# Sensor.net
KiCad netlist of a schematic drawn in Altium Designer
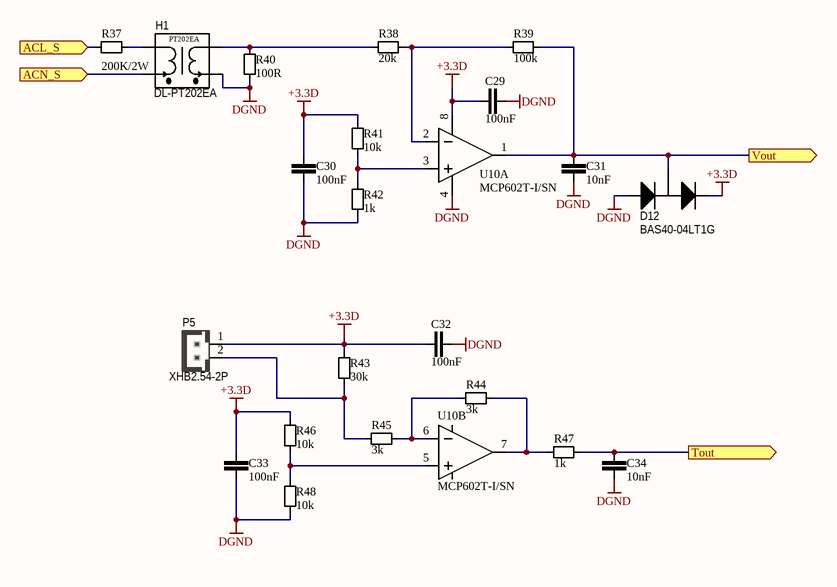
[diagram p0: Sensor.SchDoc]

(export (version "E")
  (design (tool "Eeschema 10.0.6"))
  (components
    (comp (ref "C29")
      (value "100nF")
      (footprint "GreenBox:0603-C")
      (description "MLCC 100nF 10% 50V X7R 0603")
      (fields (field (name "Comment") "Cap") (field (name "PUBLISHER") "GreenBox"))
      (libsource (lib "Capacitor") (part "C21C100NK1H0"))
    )
    (comp (ref "C30")
      (value "100nF")
      (footprint "GreenBox:0603-C")
      (description "MLCC 100nF 10% 50V X7R 0603")
      (fields (field (name "Comment") "Cap") (field (name "PUBLISHER") "GreenBox"))
      (libsource (lib "Capacitor") (part "C21C100NK1H0"))
    )
    (comp (ref "C31")
      (value "10nF")
      (footprint "GreenBox:0603-C")
      (description "MLCC 10nF 10% 50V X7R 0603")
      (fields (field (name "Comment") "Cap") (field (name "PUBLISHER") "GreenBox"))
      (libsource (lib "Capacitor") (part "C21C010NK1H0"))
    )
    (comp (ref "C32")
      (value "100nF")
      (footprint "GreenBox:0603-C")
      (description "MLCC 100nF 10% 50V X7R 0603")
      (fields (field (name "Comment") "Cap") (field (name "PUBLISHER") "GreenBox"))
      (libsource (lib "Capacitor") (part "C21C100NK1H0"))
    )
    (comp (ref "C33")
      (value "100nF")
      (footprint "GreenBox:0603-C")
      (description "MLCC 100nF 10% 50V X7R 0603")
      (fields (field (name "Comment") "Cap") (field (name "PUBLISHER") "GreenBox"))
      (libsource (lib "Capacitor") (part "C21C100NK1H0"))
    )
    (comp (ref "C34")
      (value "10nF")
      (footprint "GreenBox:0603-C")
      (description "MLCC 10nF 10% 50V X7R 0603")
      (fields (field (name "Comment") "Cap") (field (name "PUBLISHER") "GreenBox"))
      (libsource (lib "Capacitor") (part "C21C010NK1H0"))
    )
    (comp (ref "D12")
      (value "BAS40-04LT1G")
      (footprint "GreenBox:SOT-23_N")
      (description "Dual Series Schottky Barrier Diode BAS40-04LT1G Vrrm 40V If 0.12A Ir 1uA")
      (fields (field (name "MANUFACTURER") "ON SEMICONDUCTOR") (field (name "PUBLISHER") "GreenBox"))
      (libsource (lib "Diode_Transistor") (part "D742BAS4004O"))
    )
    (comp (ref "H1")
      (value "DL-PT202EA")
      (footprint "GreenBox:DL-PT202EA")
      (description "Voltage Transformer DL-PT202EA 2mA/2mA 0.1")
      (fields (field (name "MANUFACTURER") "南京向上电子科技有限公司") (field (name "PUBLISHER") "GreenBox"))
      (libsource (lib "Sensor") (part "H1DZPT202EAX"))
    )
    (comp (ref "P5")
      (value "XHB2.54-2P")
      (footprint "GreenBox:XH-2")
      (description "Header XHB2.54-2P 2.54mm")
      (fields (field (name "PUBLISHER") "GreenBox"))
      (libsource (lib "Connectors") (part "P6DX02Z25400"))
    )
    (comp (ref "R37")
      (value "200K/2W")
      (footprint "GreenBox:AXIAL-5mm")
      (description "Metal Film Resistor 200KR 1% 2W0 AXIAL 100PPM")
      (fields (field (name "Comment") "Res") (field (name "PUBLISHER") "GreenBox"))
      (libsource (lib "Resistor") (part "RMDA200KFGF0"))
    )
    (comp (ref "R38")
      (value "20k")
      (footprint "GreenBox:0603-R")
      (description "SMD Resistor 20k 1% 1/10W 0603 100PPM")
      (fields (field (name "Comment") "Res") (field (name "PUBLISHER") "GreenBox"))
      (libsource (lib "Resistor") (part "R11C020KFBF0"))
    )
    (comp (ref "R39")
      (value "100k")
      (footprint "GreenBox:0603-R")
      (description "SMD Resistor 100k 1% 1/10W 0603 100PPM")
      (fields (field (name "Comment") "Res") (field (name "PUBLISHER") "GreenBox"))
      (libsource (lib "Resistor") (part "R11C100KFBF0"))
    )
    (comp (ref "R40")
      (value "100R")
      (footprint "GreenBox:0603-R")
      (description "SMD Resistor 100R 1% 1/10W 0603 100PPM")
      (fields (field (name "Comment") "Res") (field (name "PUBLISHER") "GreenBox"))
      (libsource (lib "Resistor") (part "R11C100RFBF0"))
    )
    (comp (ref "R41")
      (value "10k")
      (footprint "GreenBox:0603-R")
      (description "SMD Resistor 10k 1% 1/10W 0603 100PPM")
      (fields (field (name "Comment") "Res") (field (name "PUBLISHER") "GreenBox"))
      (libsource (lib "Resistor") (part "R11C010KFBF0"))
    )
    (comp (ref "R42")
      (value "1k")
      (footprint "GreenBox:0603-R")
      (description "SMD Resistor 1k 1% 1/10W 0603 100PPM")
      (fields (field (name "Comment") "Res") (field (name "PUBLISHER") "GreenBox"))
      (libsource (lib "Resistor") (part "R11C001KFBF0"))
    )
    (comp (ref "R43")
      (value "30k")
      (footprint "GreenBox:0603-R")
      (description "SMD Resistor 30k 1% 1/10W 0603 100PPM")
      (fields (field (name "Comment") "Res") (field (name "PUBLISHER") "GreenBox"))
      (libsource (lib "Resistor") (part "R11C030KFBF0"))
    )
    (comp (ref "R44")
      (value "3k")
      (footprint "GreenBox:0603-R")
      (description "SMD Resistor 3k 1% 1/10W 0603 100PPM")
      (fields (field (name "Comment") "Res") (field (name "PUBLISHER") "GreenBox"))
      (libsource (lib "Resistor") (part "R11C003KFBF0"))
    )
    (comp (ref "R45")
      (value "3k")
      (footprint "GreenBox:0603-R")
      (description "SMD Resistor 3k 1% 1/10W 0603 100PPM")
      (fields (field (name "Comment") "Res") (field (name "PUBLISHER") "GreenBox"))
      (libsource (lib "Resistor") (part "R11C003KFBF0"))
    )
    (comp (ref "R46")
      (value "10k")
      (footprint "GreenBox:0603-R")
      (description "SMD Resistor 10k 1% 1/10W 0603 100PPM")
      (fields (field (name "Comment") "Res") (field (name "PUBLISHER") "GreenBox"))
      (libsource (lib "Resistor") (part "R11C010KFBF0"))
    )
    (comp (ref "R47")
      (value "1k")
      (footprint "GreenBox:0603-R")
      (description "SMD Resistor 1k 1% 1/10W 0603 100PPM")
      (fields (field (name "Comment") "Res") (field (name "PUBLISHER") "GreenBox"))
      (libsource (lib "") (part "R11C001KFBF0_1"))
    )
    (comp (ref "R48")
      (value "10k")
      (footprint "GreenBox:0603-R")
      (description "SMD Resistor 10k 1% 1/10W 0603 100PPM")
      (fields (field (name "Comment") "Res") (field (name "PUBLISHER") "GreenBox"))
      (libsource (lib "Resistor") (part "R11C010KFBF0"))
    )
    (comp (ref "U10")
      (value "MCP602T-I/SN")
      (footprint "GreenBox:SO-8_N")
      (description "Dual Rail To Rail Operational Amplifier MCP602T-I/SN Vcc 2.7V~5.5V Vio 2mV")
      (fields (field (name "MANUFACTURER") "MICROCHIP") (field (name "PUBLISHER") "GreenBox"))
      (libsource (lib "OPAMP") (part "UOS1MCP602IM"))
    )
  )
  (nets
    (net (code "1") (name "+3.3D") (class "Default")
      (node (ref "C29") (pin "1") (pinfunction "1_1") (pintype "passive"))
      (node (ref "C30") (pin "1") (pinfunction "1_1") (pintype "passive"))
      (node (ref "C32") (pin "1") (pinfunction "1_1") (pintype "passive"))
      (node (ref "C33") (pin "1") (pinfunction "1_1") (pintype "passive"))
      (node (ref "D12") (pin "2") (pinfunction "K_2") (pintype "passive"))
      (node (ref "P5") (pin "1") (pinfunction "1_1") (pintype "passive"))
      (node (ref "R41") (pin "1") (pinfunction "1_1") (pintype "passive"))
      (node (ref "R43") (pin "1") (pinfunction "1_1") (pintype "passive"))
      (node (ref "R46") (pin "1") (pinfunction "1_1") (pintype "passive"))
      (node (ref "U10") (pin "8") (pintype "passive"))
    )
    (net (code "2") (name "/ACL_S") (class "Default")
      (node (ref "R37") (pin "1") (pinfunction "1_1") (pintype "passive"))
    )
    (net (code "3") (name "/ACN_S") (class "Default")
      (node (ref "H1") (pin "1") (pinfunction "1_1") (pintype "passive"))
    )
    (net (code "4") (name "/Tout") (class "Default")
      (node (ref "C34") (pin "1") (pinfunction "1_1") (pintype "passive"))
      (node (ref "R47") (pin "2") (pinfunction "2_2") (pintype "passive"))
    )
    (net (code "5") (name "/Vout") (class "Default")
      (node (ref "C31") (pin "1") (pinfunction "1_1") (pintype "passive"))
      (node (ref "D12") (pin "3") (pinfunction "C_3") (pintype "passive"))
      (node (ref "R39") (pin "2") (pinfunction "2_2") (pintype "passive"))
      (node (ref "U10") (pin "1") (pintype "passive"))
    )
    (net (code "6") (name "DGND") (class "Default")
      (node (ref "C29") (pin "2") (pinfunction "2_2") (pintype "passive"))
      (node (ref "C30") (pin "2") (pinfunction "2_2") (pintype "passive"))
      (node (ref "C31") (pin "2") (pinfunction "2_2") (pintype "passive"))
      (node (ref "C32") (pin "2") (pinfunction "2_2") (pintype "passive"))
      (node (ref "C33") (pin "2") (pinfunction "2_2") (pintype "passive"))
      (node (ref "C34") (pin "2") (pinfunction "2_2") (pintype "passive"))
      (node (ref "D12") (pin "1") (pinfunction "A_1") (pintype "passive"))
      (node (ref "H1") (pin "4") (pinfunction "4_4") (pintype "passive"))
      (node (ref "R40") (pin "1") (pinfunction "1_1") (pintype "passive"))
      (node (ref "R42") (pin "1") (pinfunction "1_1") (pintype "passive"))
      (node (ref "R48") (pin "2") (pinfunction "2_2") (pintype "passive"))
      (node (ref "U10") (pin "4") (pintype "passive"))
    )
    (net (code "7") (name "Net-(H1-Pad2)") (class "Default")
      (node (ref "H1") (pin "2") (pinfunction "2_2") (pintype "passive"))
      (node (ref "R37") (pin "2") (pinfunction "2_2") (pintype "passive"))
    )
    (net (code "8") (name "Net-(H1-Pad3)") (class "Default")
      (node (ref "H1") (pin "3") (pinfunction "3_3") (pintype "passive"))
      (node (ref "R38") (pin "2") (pinfunction "2_2") (pintype "passive"))
      (node (ref "R40") (pin "2") (pinfunction "2_2") (pintype "passive"))
    )
    (net (code "9") (name "Net-(P5-Pad2)") (class "Default")
      (node (ref "P5") (pin "2") (pinfunction "2_2") (pintype "passive"))
      (node (ref "R43") (pin "2") (pinfunction "2_2") (pintype "passive"))
      (node (ref "R45") (pin "1") (pinfunction "1_1") (pintype "passive"))
    )
    (net (code "10") (name "Net-(R38-Pad1)") (class "Default")
      (node (ref "R38") (pin "1") (pinfunction "1_1") (pintype "passive"))
      (node (ref "R39") (pin "1") (pinfunction "1_1") (pintype "passive"))
      (node (ref "U10") (pin "2") (pintype "passive"))
    )
    (net (code "11") (name "Net-(R41-Pad2)") (class "Default")
      (node (ref "R41") (pin "2") (pinfunction "2_2") (pintype "passive"))
      (node (ref "R42") (pin "2") (pinfunction "2_2") (pintype "passive"))
      (node (ref "U10") (pin "3") (pintype "passive"))
    )
    (net (code "12") (name "Net-(R44-Pad1)") (class "Default")
      (node (ref "R44") (pin "1") (pinfunction "1_1") (pintype "passive"))
      (node (ref "R45") (pin "2") (pinfunction "2_2") (pintype "passive"))
      (node (ref "U10") (pin "6") (pintype "passive"))
    )
    (net (code "13") (name "Net-(R44-Pad2)") (class "Default")
      (node (ref "R44") (pin "2") (pinfunction "2_2") (pintype "passive"))
      (node (ref "R47") (pin "1") (pinfunction "1_1") (pintype "passive"))
      (node (ref "U10") (pin "7") (pintype "passive"))
    )
    (net (code "14") (name "Net-(R46-Pad2)") (class "Default")
      (node (ref "R46") (pin "2") (pinfunction "2_2") (pintype "passive"))
      (node (ref "R48") (pin "1") (pinfunction "1_1") (pintype "passive"))
      (node (ref "U10") (pin "5") (pintype "passive"))
    )
  )
)
